# CATS-EUROC-Pyro.net
KiCad netlist of a schematic drawn in Altium Designer
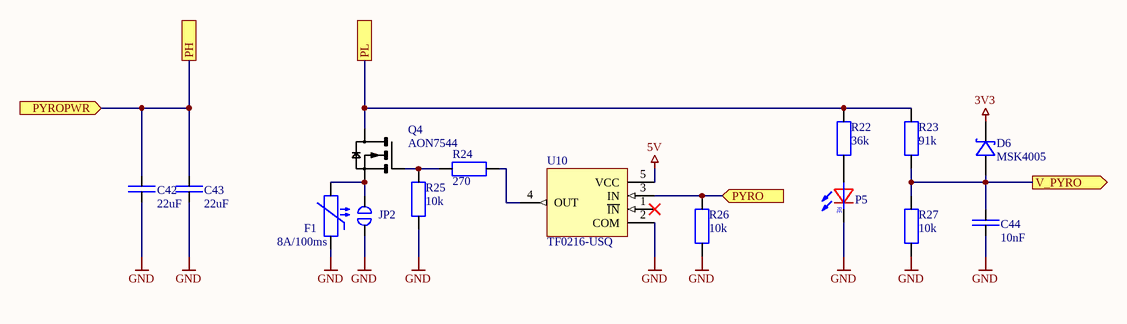
[diagram p0: CATS-EUROC-Pyro.SchDoc]

(export (version "E")
  (design (tool "Eeschema 10.0.6"))
  (components
    (comp (ref "C42")
      (value "22uF")
      (footprint "SMD Keramikkondensator 0805")
      (description "SMD Ceramic Capacitor E6")
      (libsource (lib "CATS-EUROC") (part "E6 - 22uF"))
    )
    (comp (ref "C43")
      (value "22uF")
      (footprint "SMD Keramikkondensator 0805")
      (description "SMD Ceramic Capacitor E6")
      (libsource (lib "CATS-EUROC") (part "E6 - 22uF"))
    )
    (comp (ref "C44")
      (value "10nF")
      (footprint "SMD Keramikkondensator 0402")
      (description "SMD Ceramic Capacitor E6")
      (libsource (lib "CATS-EUROC") (part "E6 - 10nF"))
    )
    (comp (ref "D6")
      (value "MSK4005")
      (footprint "SMD Diode SOD-523")
      (description "SOD-523 Schottky Barrier Diode")
      (libsource (lib "Diodes") (part "MSK4005"))
    )
    (comp (ref "F1")
      (value "8A/100ms")
      (footprint "SMD PPTC-Fuse 1206")
      (description "16V 1A 100A 1.8A 1206 Resettable")
      (libsource (lib "Other") (part "nSMD100-16V"))
    )
    (comp (ref "JP2")
      (value "Jumper")
      (footprint "SMD Solder Jumper 1x2mm")
      (description "Single Position Jumper")
      (libsource (lib "Connectors") (part "Jumper-1"))
    )
    (comp (ref "P5")
      (value "LED")
      (footprint "SMD LED 0603")
      (description "Color LED")
      (libsource (lib "Diodes") (part "LED"))
    )
    (comp (ref "Q4")
      (value "AON7544")
      (footprint "SMD MOSFET DFN 3x3 EP")
      (description "N-Channel 30V 30A Surface Mount 8-DFN (3x3)")
      (libsource (lib "Electronic Switches") (part "AON7544"))
    )
    (comp (ref "R22")
      (value "36k")
      (footprint "SMD Widerstand 0402")
      (description "SMD Chip Resistor E24")
      (libsource (lib "CATS-EUROC") (part "E24 - 36k"))
    )
    (comp (ref "R23")
      (value "91k")
      (footprint "SMD Widerstand 0402")
      (description "SMD Chip Resistor E24")
      (libsource (lib "CATS-EUROC") (part "E24 - 91k"))
    )
    (comp (ref "R24")
      (value "270")
      (footprint "SMD Widerstand 0402")
      (description "SMD Chip Resistor E24")
      (libsource (lib "CATS-EUROC") (part "E24 - 270"))
    )
    (comp (ref "R25")
      (value "10k")
      (footprint "SMD Widerstand 0402")
      (description "SMD Chip Resistor E24")
      (libsource (lib "CATS-EUROC") (part "E24 - 10k"))
    )
    (comp (ref "R26")
      (value "10k")
      (footprint "SMD Widerstand 0402")
      (description "SMD Chip Resistor E24")
      (libsource (lib "CATS-EUROC") (part "E24 - 10k"))
    )
    (comp (ref "R27")
      (value "10k")
      (footprint "SMD Widerstand 0402")
      (description "SMD Chip Resistor E24")
      (libsource (lib "CATS-EUROC") (part "E24 - 10k"))
    )
    (comp (ref "U10")
      (value "TF0216-USQ")
      (footprint "SMD IC SOT-23-5")
      (description "SOT-23-5L Gate Drive IC")
      (libsource (lib "Electronic Switches") (part "TF0216-USQ"))
    )
  )
  (nets
    (net (code "1") (name "/PH") (class "Default")
      (node (ref "C42") (pin "2") (pinfunction "2_2") (pintype "passive"))
      (node (ref "C43") (pin "2") (pinfunction "2_2") (pintype "passive"))
    )
    (net (code "2") (name "/PL") (class "Default")
      (node (ref "Q4") (pin "D") (pinfunction "D_D") (pintype "passive"))
      (node (ref "R22") (pin "2") (pinfunction "2_2") (pintype "passive"))
      (node (ref "R23") (pin "2") (pinfunction "2_2") (pintype "passive"))
    )
    (net (code "3") (name "/PYRO") (class "Default")
      (node (ref "R26") (pin "2") (pinfunction "2_2") (pintype "passive"))
      (node (ref "U10") (pin "3") (pinfunction "IN_3") (pintype "input"))
    )
    (net (code "4") (name "/V_PYRO") (class "Default")
      (node (ref "C44") (pin "2") (pinfunction "2_2") (pintype "passive"))
      (node (ref "D6") (pin "A") (pinfunction "A_A") (pintype "passive"))
      (node (ref "R23") (pin "1") (pinfunction "1_1") (pintype "passive"))
      (node (ref "R27") (pin "2") (pinfunction "2_2") (pintype "passive"))
    )
    (net (code "5") (name "3V3") (class "Default")
      (node (ref "D6") (pin "K") (pinfunction "K_K") (pintype "passive"))
    )
    (net (code "6") (name "5V") (class "Default")
      (node (ref "U10") (pin "5") (pinfunction "VCC_5") (pintype "passive"))
    )
    (net (code "7") (name "GND") (class "Default")
      (node (ref "C42") (pin "1") (pinfunction "1_1") (pintype "passive"))
      (node (ref "C43") (pin "1") (pinfunction "1_1") (pintype "passive"))
      (node (ref "C44") (pin "1") (pinfunction "1_1") (pintype "passive"))
      (node (ref "F1") (pin "2") (pinfunction "2_2") (pintype "passive"))
      (node (ref "JP2") (pin "2") (pintype "passive"))
      (node (ref "P5") (pin "K") (pinfunction "K_K") (pintype "passive"))
      (node (ref "R25") (pin "1") (pinfunction "1_1") (pintype "passive"))
      (node (ref "R26") (pin "1") (pinfunction "1_1") (pintype "passive"))
      (node (ref "R27") (pin "1") (pinfunction "1_1") (pintype "passive"))
      (node (ref "U10") (pin "2") (pinfunction "COM_2") (pintype "passive"))
    )
    (net (code "8") (name "Net-(F1-Pad1)") (class "Default")
      (node (ref "F1") (pin "1") (pinfunction "1_1") (pintype "passive"))
      (node (ref "JP2") (pin "1") (pintype "passive"))
      (node (ref "Q4") (pin "S") (pinfunction "S_S") (pintype "passive"))
    )
    (net (code "9") (name "Net-(P5-PadA)") (class "Default")
      (node (ref "P5") (pin "A") (pinfunction "A_A") (pintype "passive"))
      (node (ref "R22") (pin "1") (pinfunction "1_1") (pintype "passive"))
    )
    (net (code "10") (name "Net-(Q4-PadG)") (class "Default")
      (node (ref "Q4") (pin "G") (pinfunction "G_G") (pintype "passive"))
      (node (ref "R24") (pin "1") (pinfunction "1_1") (pintype "passive"))
      (node (ref "R25") (pin "2") (pinfunction "2_2") (pintype "passive"))
    )
    (net (code "11") (name "Net-(U10-OUT)") (class "Default")
      (node (ref "R24") (pin "2") (pinfunction "2_2") (pintype "passive"))
      (node (ref "U10") (pin "4") (pinfunction "OUT_4") (pintype "output"))
    )
    (net (code "12") (name "unconnected-(U10-~{IN}-Pad1)") (class "Default")
      (node (ref "U10") (pin "1") (pinfunction "~{IN}_1") (pintype "input+no_connect"))
    )
  )
)
